# Actuator.net
KiCad netlist of a schematic drawn in Altium Designer
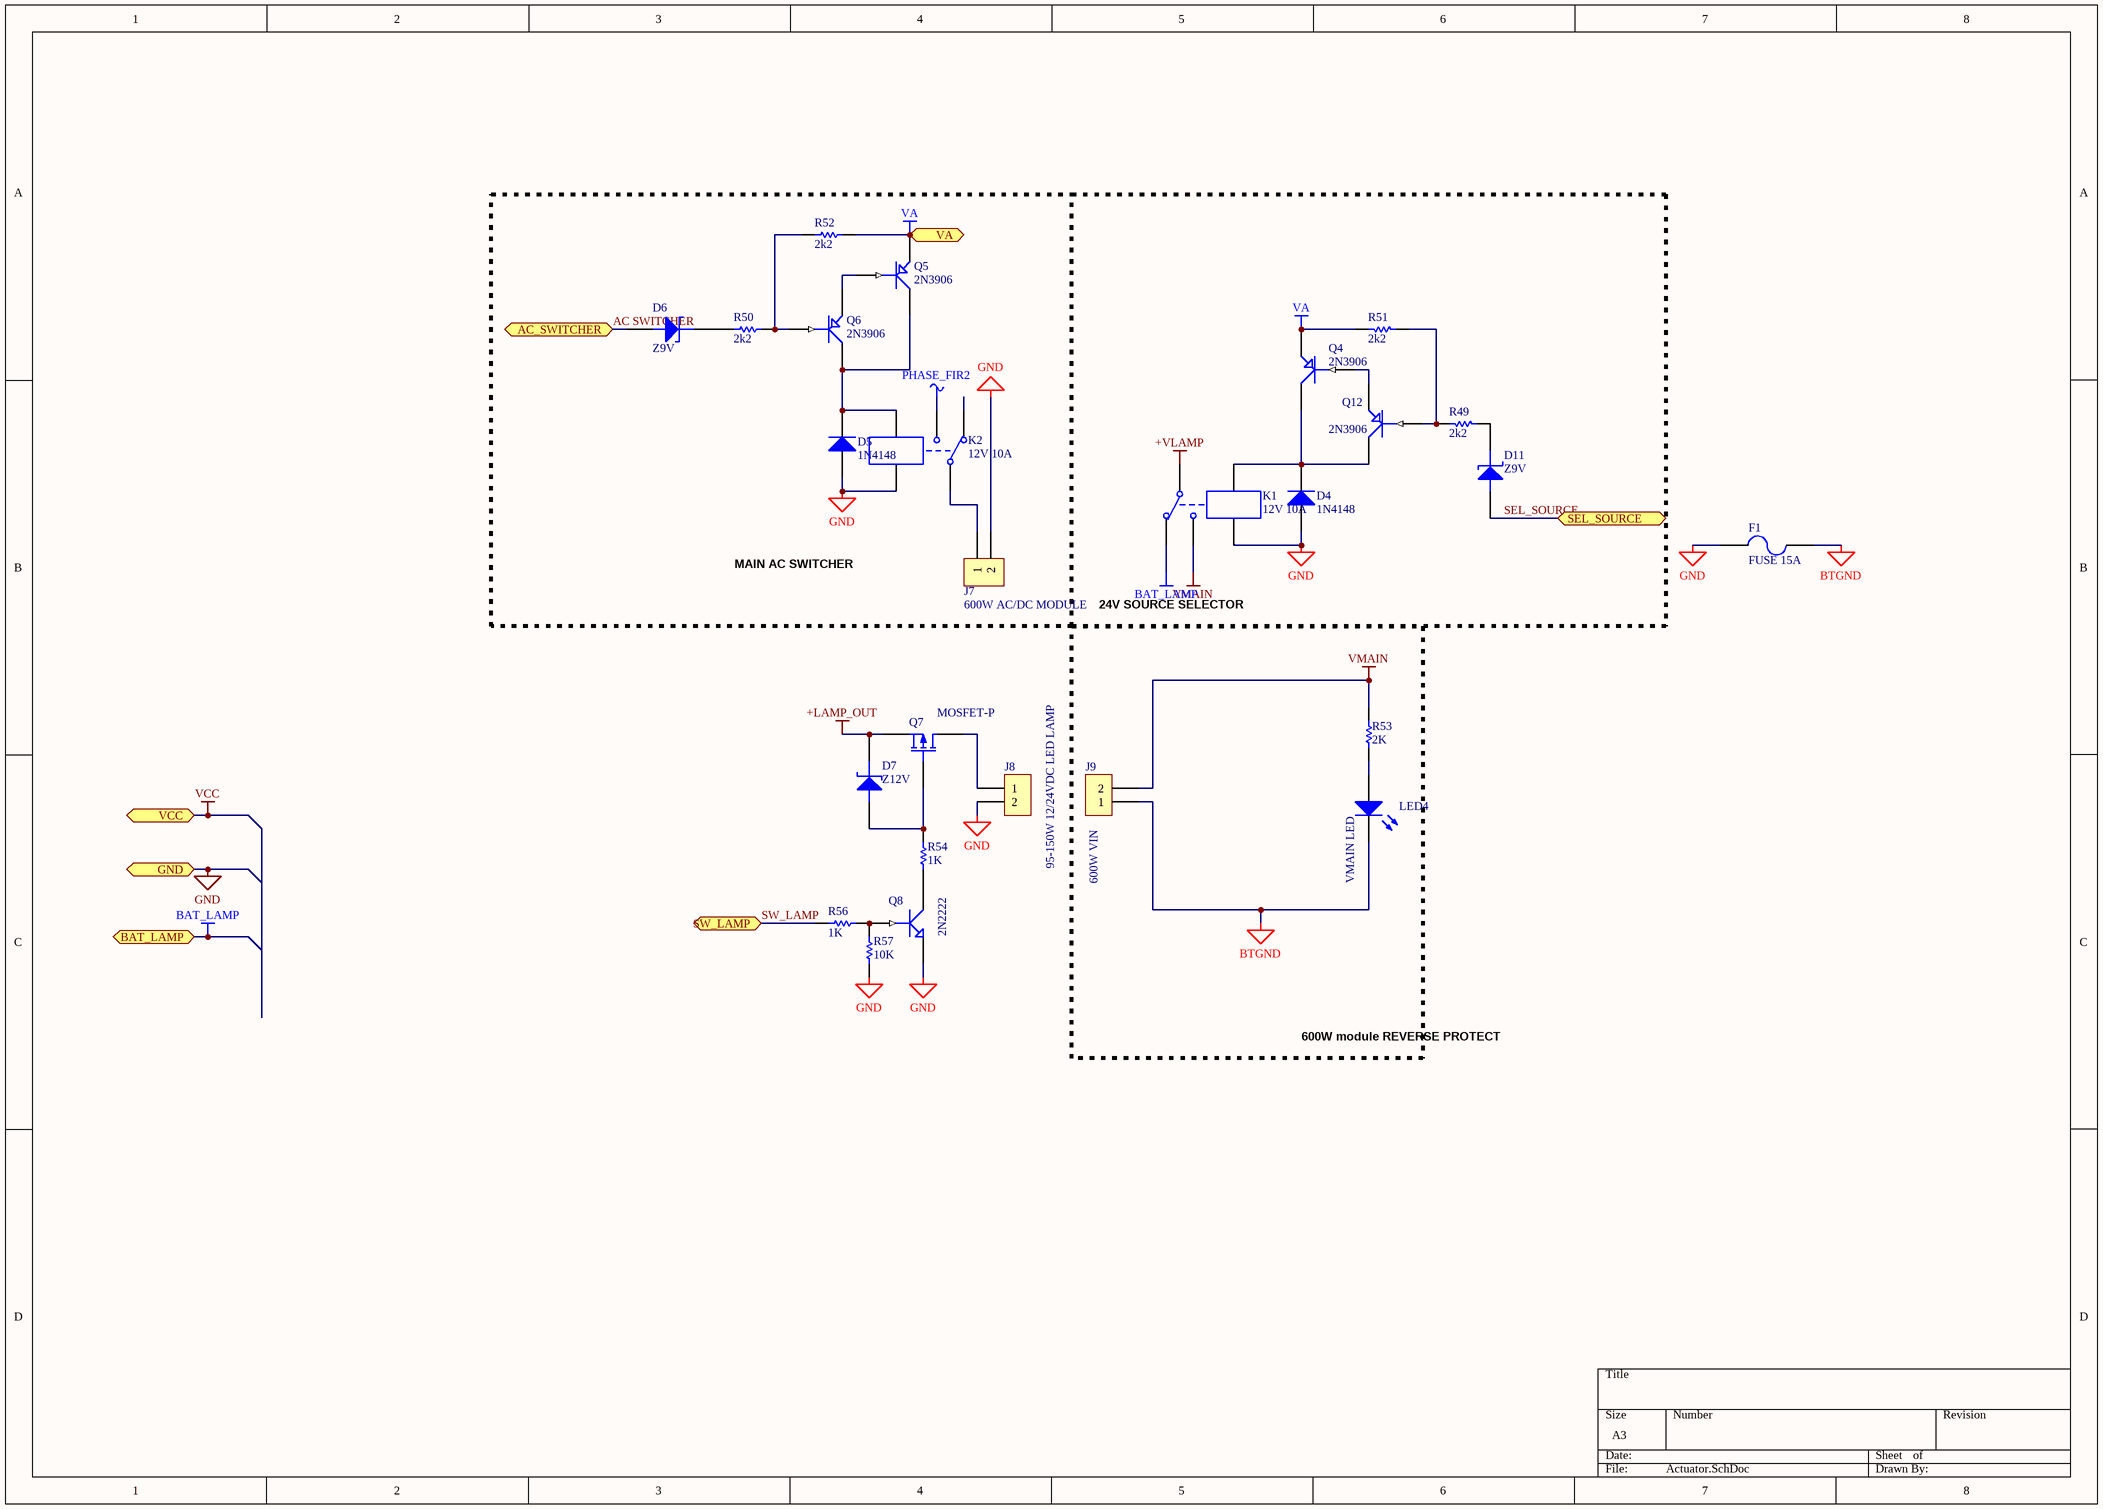
[diagram p0: Actuator.SchDoc]

(export (version "E")
  (design (tool "Eeschema 10.0.6"))
  (components
    (comp (ref "D4")
      (value "1N4148")
      (footprint "SOD-80/MLL34")
      (description "1 Amp General Purpose Rectifier")
      (fields (field (name "PUBLISHER") "Altium Limited"))
      (libsource (lib "*") (part "Diode 1N4007"))
    )
    (comp (ref "D5")
      (value "1N4148")
      (footprint "SOD-80/MLL34")
      (description "1 Amp General Purpose Rectifier")
      (fields (field (name "PUBLISHER") "Altium Limited"))
      (libsource (lib "*") (part "Diode 1N4007"))
    )
    (comp (ref "D6")
      (value "Z9V")
      (footprint "SOD-80/MLL34")
      (description "Zener Diode")
      (libsource (lib "*") (part "ZENER2"))
    )
    (comp (ref "D7")
      (value "Z12V")
      (footprint "SOD-80/MLL34")
      (description "Zener Diode")
      (libsource (lib "*") (part "ZENER2"))
    )
    (comp (ref "D11")
      (value "Z9V")
      (footprint "SOD-80/MLL34")
      (description "Zener Diode")
      (libsource (lib "*") (part "ZENER2"))
    )
    (comp (ref "F1")
      (value "FUSE 15A")
      (footprint "FUSE2")
      (description "Fuse")
      (libsource (lib "*") (part "FUSE2"))
    )
    (comp (ref "J7")
      (value "600W AC/DC MODULE")
      (footprint "TERMINAL2")
      (description "Connector")
      (libsource (lib "") (part "CON2_1"))
    )
    (comp (ref "J8")
      (value "95-150W 12/24VDC LED LAMP")
      (footprint "TERMINAL2")
      (description "Connector")
      (libsource (lib "*") (part "CON2"))
    )
    (comp (ref "J9")
      (value "600W VIN")
      (footprint "TERMINAL2")
      (description "Connector")
      (libsource (lib "") (part "CON2_1"))
    )
    (comp (ref "K1")
      (value "12V 10A")
      (footprint "RELAYVUONG")
      (description "G5LA-10A/250VAC / SRC-12VDC-SL-C")
      (fields (field (name "PUBLISHER") "Altium Limited"))
      (libsource (lib "Miscellaneous Devices") (part "Relay-SPDT"))
    )
    (comp (ref "K2")
      (value "12V 10A")
      (footprint "RELAYVUONG")
      (description "G5LA-10A/250VAC / SRC-12VDC-SL-C")
      (fields (field (name "PUBLISHER") "Altium Limited"))
      (libsource (lib "Miscellaneous Devices") (part "Relay-SPDT"))
    )
    (comp (ref "LED4")
      (value "VMAIN LED")
      (footprint "SMD _LED")
      (description "Typical BLUE SiC LED")
      (fields (field (name "PUBLISHER") "Altium Limited"))
      (libsource (lib "Miscellaneous Devices") (part "LED3"))
    )
    (comp (ref "Q4")
      (value "2N3906")
      (footprint "SOT-23")
      (description "PNP Transistor")
      (libsource (lib "*") (part "PNP1"))
    )
    (comp (ref "Q5")
      (value "2N3906")
      (footprint "SOT-23")
      (description "PNP Transistor")
      (libsource (lib "*") (part "PNP1"))
    )
    (comp (ref "Q6")
      (value "2N3906")
      (footprint "SOT-23")
      (description "PNP Transistor")
      (libsource (lib "*") (part "PNP1"))
    )
    (comp (ref "Q7")
      (value "MOSFET-P")
      (footprint "TO254P1420-3_4M")
      (description "P-Channel MOSFET")
      (fields (field (name "PUBLISHER") "Altium Limited"))
      (libsource (lib "Miscellaneous Devices") (part "MOSFET-P"))
    )
    (comp (ref "Q8")
      (value "2N2222")
      (footprint "SOT-23")
      (description "NPN Transistor")
      (libsource (lib "*") (part "NPN1"))
    )
    (comp (ref "Q12")
      (value "2N3906")
      (footprint "SOT-23")
      (description "PNP Transistor")
      (libsource (lib "*") (part "PNP1"))
    )
    (comp (ref "R49")
      (value "2k2")
      (footprint "2012[0805]")
      (description "Semiconductor Resistor")
      (fields (field (name "PUBLISHER") "Altium Limited"))
      (libsource (lib "*") (part "Res Semi"))
    )
    (comp (ref "R50")
      (value "2k2")
      (footprint "2012[0805]")
      (description "Semiconductor Resistor")
      (fields (field (name "PUBLISHER") "Altium Limited"))
      (libsource (lib "*") (part "Res Semi"))
    )
    (comp (ref "R51")
      (value "2k2")
      (footprint "2012[0805]")
      (description "Semiconductor Resistor")
      (fields (field (name "PUBLISHER") "Altium Limited"))
      (libsource (lib "*") (part "Res Semi"))
    )
    (comp (ref "R52")
      (value "2k2")
      (footprint "2012[0805]")
      (description "Semiconductor Resistor")
      (fields (field (name "PUBLISHER") "Altium Limited"))
      (libsource (lib "*") (part "Res Semi"))
    )
    (comp (ref "R53")
      (value "2K")
      (footprint "6-0805_N")
      (description "Semiconductor Resistor")
      (fields (field (name "PUBLISHER") "*"))
      (libsource (lib "*") (part "Res Semi"))
    )
    (comp (ref "R54")
      (value "1K")
      (footprint "6-0805_N")
      (description "Semiconductor Resistor")
      (fields (field (name "PUBLISHER") "Altium Limited"))
      (libsource (lib "*") (part "Res Semi"))
    )
    (comp (ref "R56")
      (value "1K")
      (footprint "6-0805_N")
      (description "Semiconductor Resistor")
      (fields (field (name "PUBLISHER") "Altium Limited"))
      (libsource (lib "*") (part "Res Semi"))
    )
    (comp (ref "R57")
      (value "10K")
      (footprint "6-0805_N")
      (description "Semiconductor Resistor")
      (fields (field (name "PUBLISHER") "Altium Limited"))
      (libsource (lib "*") (part "Res Semi"))
    )
  )
  (nets
    (net (code "1") (name "+LAMP_OUT") (class "Default")
      (node (ref "D7") (pin "2") (pinfunction "K_2") (pintype "passive"))
      (node (ref "Q7") (pin "3") (pinfunction "S_3") (pintype "passive"))
    )
    (net (code "2") (name "+VLAMP") (class "Default")
      (node (ref "K1") (pin "1") (pinfunction "1_1") (pintype "passive"))
    )
    (net (code "3") (name "/AC SWITCHER") (class "Default")
      (node (ref "D6") (pin "1") (pinfunction "A_1") (pintype "passive"))
    )
    (net (code "4") (name "/SEL_SOURCE") (class "Default")
      (node (ref "D11") (pin "1") (pinfunction "A_1") (pintype "passive"))
    )
    (net (code "5") (name "/SW_LAMP") (class "Default")
      (node (ref "R56") (pin "1") (pinfunction "1_1") (pintype "passive"))
    )
    (net (code "6") (name "BAT_LAMP") (class "Default")
      (node (ref "K1") (pin "2") (pinfunction "2_2") (pintype "passive"))
    )
    (net (code "7") (name "BTGND") (class "Default")
      (node (ref "F1") (pin "2") (pinfunction "2_2") (pintype "passive"))
      (node (ref "J9") (pin "1") (pinfunction "1_1") (pintype "passive"))
      (node (ref "LED4") (pin "2") (pinfunction "K_2") (pintype "passive"))
    )
    (net (code "8") (name "GND") (class "Default")
      (node (ref "D4") (pin "1") (pinfunction "A_1") (pintype "passive"))
      (node (ref "D5") (pin "1") (pinfunction "A_1") (pintype "passive"))
      (node (ref "F1") (pin "1") (pinfunction "1_1") (pintype "passive"))
      (node (ref "J7") (pin "2") (pinfunction "2_2") (pintype "passive"))
      (node (ref "J8") (pin "2") (pinfunction "2_2") (pintype "passive"))
      (node (ref "K1") (pin "5") (pinfunction "5_5") (pintype "passive"))
      (node (ref "K2") (pin "4") (pinfunction "4_4") (pintype "passive"))
      (node (ref "Q8") (pin "2") (pinfunction "E_2") (pintype "passive"))
      (node (ref "R57") (pin "1") (pinfunction "1_1") (pintype "passive"))
    )
    (net (code "9") (name "Net-(D4-K)") (class "Default")
      (node (ref "D4") (pin "2") (pinfunction "K_2") (pintype "passive"))
      (node (ref "K1") (pin "4") (pinfunction "4_4") (pintype "passive"))
      (node (ref "Q12") (pin "3") (pinfunction "C_3") (pintype "passive"))
      (node (ref "Q4") (pin "3") (pinfunction "C_3") (pintype "passive"))
    )
    (net (code "10") (name "Net-(D5-K)") (class "Default")
      (node (ref "D5") (pin "2") (pinfunction "K_2") (pintype "passive"))
      (node (ref "K2") (pin "5") (pinfunction "5_5") (pintype "passive"))
      (node (ref "Q5") (pin "3") (pinfunction "C_3") (pintype "passive"))
      (node (ref "Q6") (pin "3") (pinfunction "C_3") (pintype "passive"))
    )
    (net (code "11") (name "Net-(D6-K)") (class "Default")
      (node (ref "D6") (pin "2") (pinfunction "K_2") (pintype "passive"))
      (node (ref "R50") (pin "1") (pinfunction "1_1") (pintype "passive"))
    )
    (net (code "12") (name "Net-(D7-A)") (class "Default")
      (node (ref "D7") (pin "1") (pinfunction "A_1") (pintype "passive"))
      (node (ref "Q7") (pin "1") (pinfunction "G_1") (pintype "passive"))
      (node (ref "R54") (pin "2") (pinfunction "2_2") (pintype "passive"))
    )
    (net (code "13") (name "Net-(D11-K)") (class "Default")
      (node (ref "D11") (pin "2") (pinfunction "K_2") (pintype "passive"))
      (node (ref "R49") (pin "1") (pinfunction "1_1") (pintype "passive"))
    )
    (net (code "14") (name "Net-(J7-Pad1)") (class "Default")
      (node (ref "J7") (pin "1") (pinfunction "1_1") (pintype "passive"))
      (node (ref "K2") (pin "1") (pinfunction "1_1") (pintype "passive"))
    )
    (net (code "15") (name "Net-(LED4-A)") (class "Default")
      (node (ref "LED4") (pin "1") (pinfunction "A_1") (pintype "passive"))
      (node (ref "R53") (pin "1") (pinfunction "1_1") (pintype "passive"))
    )
    (net (code "16") (name "Net-(Q5-B)") (class "Default")
      (node (ref "Q5") (pin "1") (pinfunction "B_1") (pintype "input"))
      (node (ref "Q6") (pin "2") (pinfunction "E_2") (pintype "passive"))
    )
    (net (code "17") (name "Net-(Q6-B)") (class "Default")
      (node (ref "Q6") (pin "1") (pinfunction "B_1") (pintype "input"))
      (node (ref "R50") (pin "2") (pinfunction "2_2") (pintype "passive"))
      (node (ref "R52") (pin "1") (pinfunction "1_1") (pintype "passive"))
    )
    (net (code "18") (name "Net-(Q7-D)") (class "Default")
      (node (ref "J8") (pin "1") (pinfunction "1_1") (pintype "passive"))
      (node (ref "Q7") (pin "2") (pinfunction "D_2") (pintype "passive"))
    )
    (net (code "19") (name "Net-(Q8-B)") (class "Default")
      (node (ref "Q8") (pin "1") (pinfunction "B_1") (pintype "input"))
      (node (ref "R56") (pin "2") (pinfunction "2_2") (pintype "passive"))
      (node (ref "R57") (pin "2") (pinfunction "2_2") (pintype "passive"))
    )
    (net (code "20") (name "Net-(Q8-C)") (class "Default")
      (node (ref "Q8") (pin "3") (pinfunction "C_3") (pintype "passive"))
      (node (ref "R54") (pin "1") (pinfunction "1_1") (pintype "passive"))
    )
    (net (code "21") (name "Net-(Q12-B)") (class "Default")
      (node (ref "Q12") (pin "1") (pinfunction "B_1") (pintype "input"))
      (node (ref "R49") (pin "2") (pinfunction "2_2") (pintype "passive"))
      (node (ref "R51") (pin "1") (pinfunction "1_1") (pintype "passive"))
    )
    (net (code "22") (name "Net-(Q12-E)") (class "Default")
      (node (ref "Q12") (pin "2") (pinfunction "E_2") (pintype "passive"))
      (node (ref "Q4") (pin "1") (pinfunction "B_1") (pintype "input"))
    )
    (net (code "23") (name "PHASE_FIR2") (class "Default")
      (node (ref "K2") (pin "3") (pinfunction "3_3") (pintype "passive"))
    )
    (net (code "24") (name "VA") (class "Default")
      (node (ref "Q4") (pin "2") (pinfunction "E_2") (pintype "passive"))
      (node (ref "Q5") (pin "2") (pinfunction "E_2") (pintype "passive"))
      (node (ref "R51") (pin "2") (pinfunction "2_2") (pintype "passive"))
      (node (ref "R52") (pin "2") (pinfunction "2_2") (pintype "passive"))
    )
    (net (code "26") (name "VMAIN") (class "Default")
      (node (ref "J9") (pin "2") (pinfunction "2_2") (pintype "passive"))
      (node (ref "K1") (pin "3") (pinfunction "3_3") (pintype "passive"))
      (node (ref "R53") (pin "2") (pinfunction "2_2") (pintype "passive"))
    )
    (net (code "27") (name "unconnected-(K2-Pad2)") (class "Default")
      (node (ref "K2") (pin "2") (pinfunction "2_2") (pintype "passive"))
    )
  )
)
